# Main.net
KiCad netlist of a schematic drawn in EAGLE
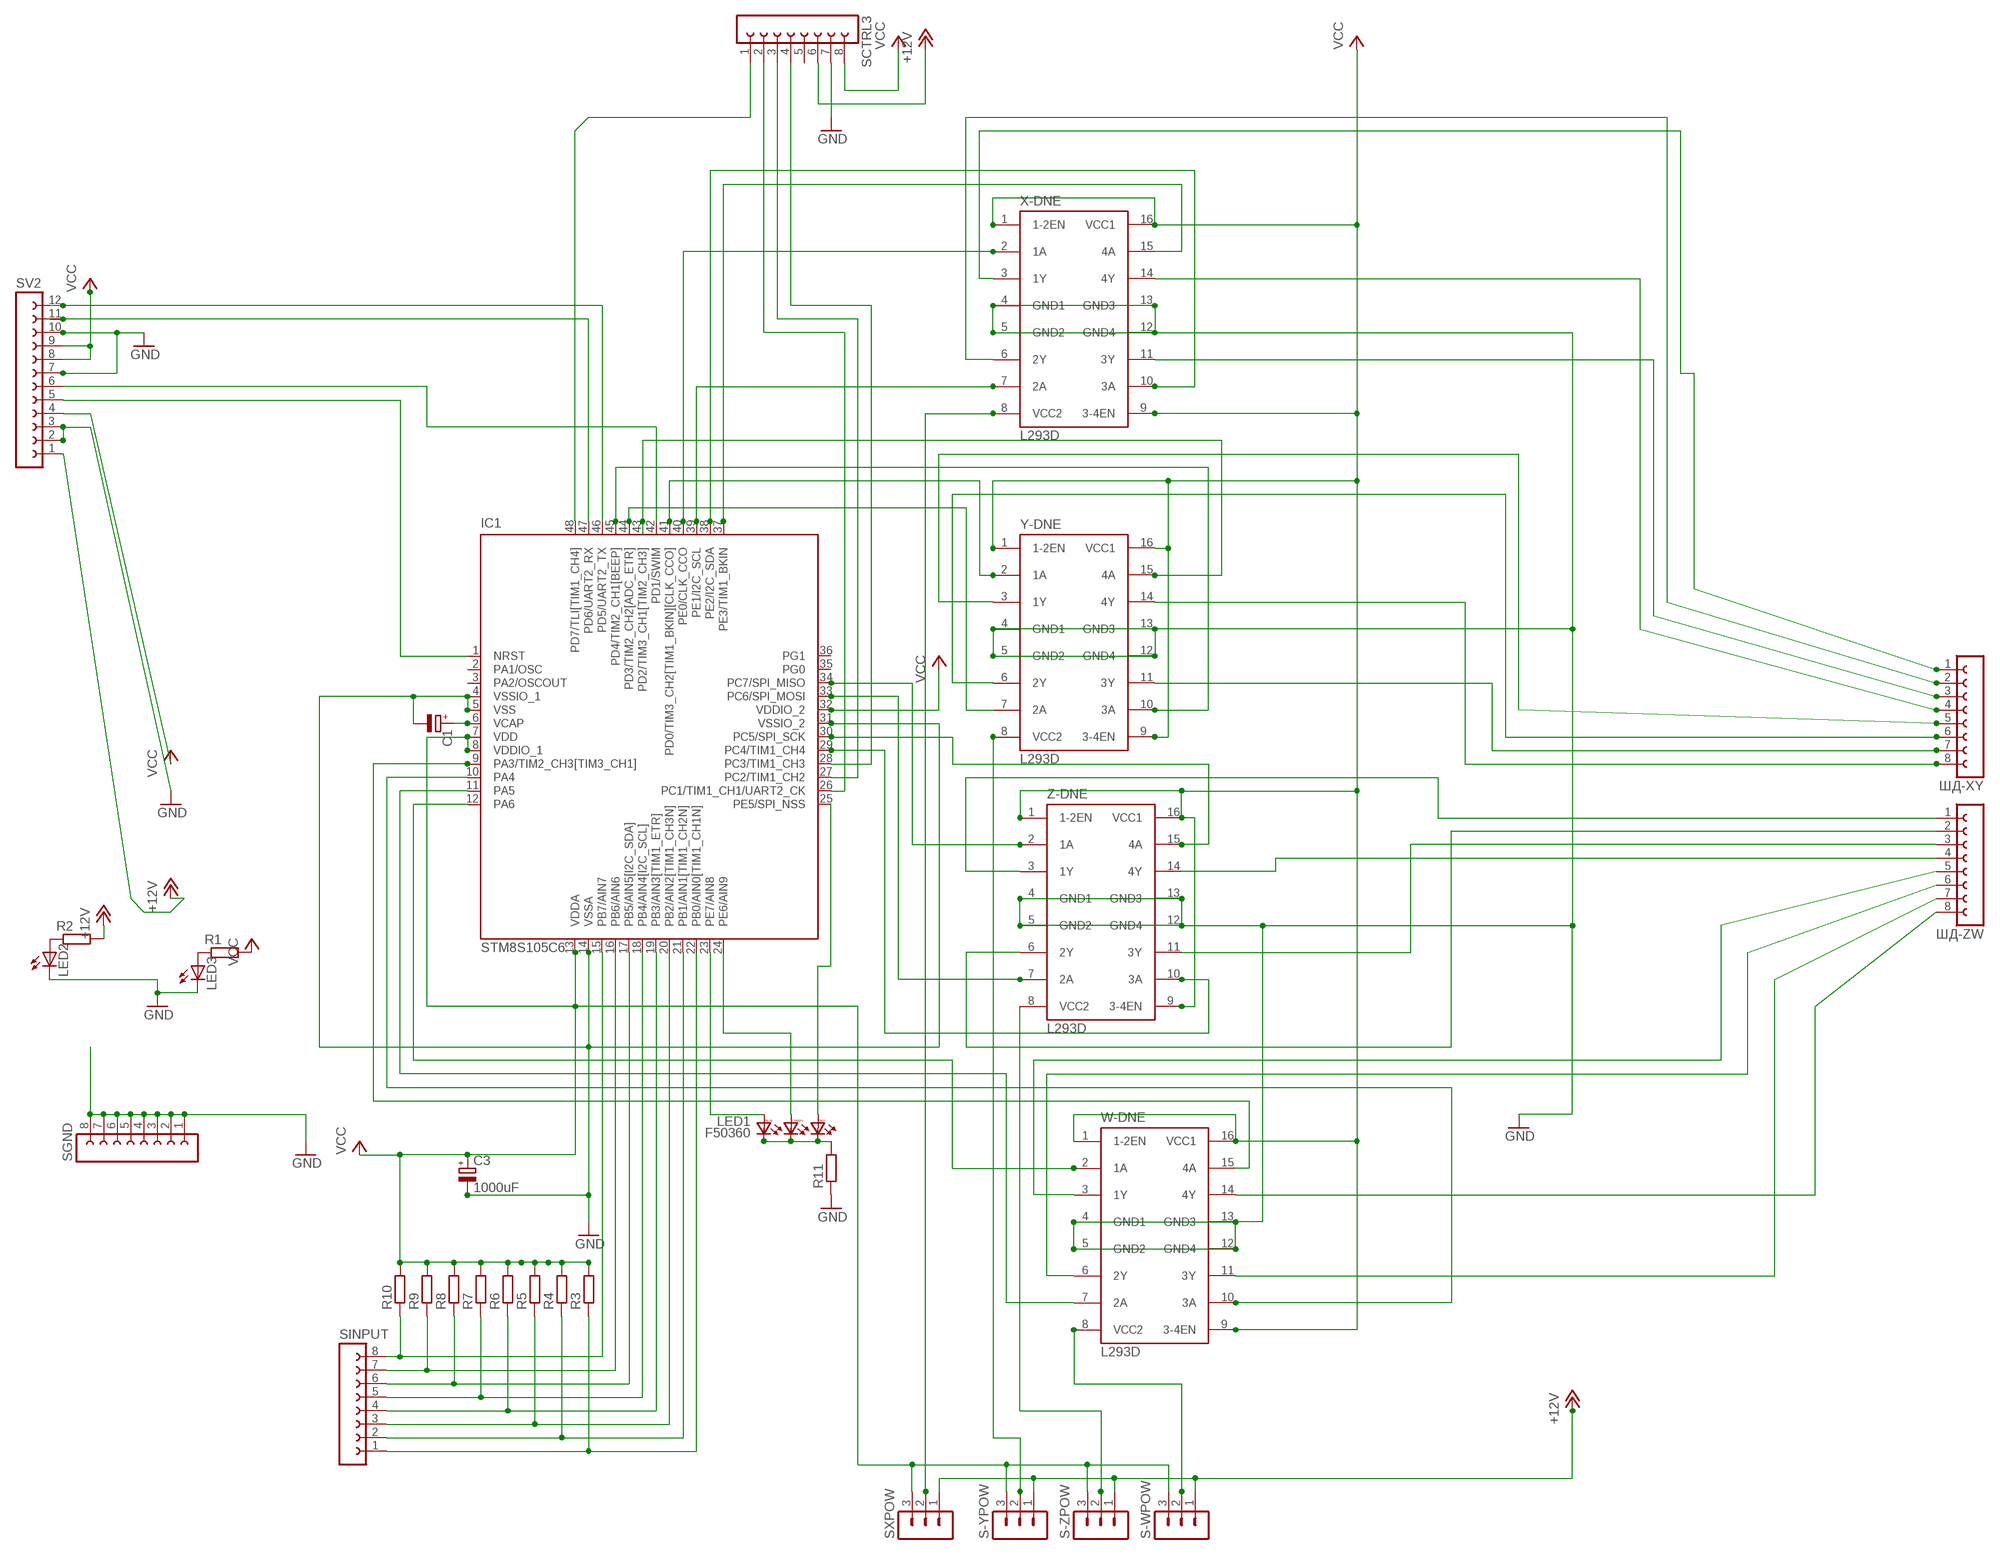
[diagram p0: schematic, sheet 1]

(export (version "E")
  (design (tool "Eeschema 10.0.6"))
  (components
    (comp (ref "C1")
      (value "CPOL-EU085CS-1AR")
      (footprint "eagle-import:085CS_1AR")
      (libsource (lib "eagle-import") (part "resistor_CPOL-EU085CS-1AR"))
    )
    (comp (ref "C3")
      (value "1000uF")
      (footprint "eagle-import:SANYO-OSCON_9E")
      (libsource (lib "eagle-import") (part "CPOL-EUSANYO_9E"))
    )
    (comp (ref "IC1")
      (value "STM8S105C6")
      (footprint "eagle-import:LQFP48-7X7")
      (fields (field (name "MPN") "STM8S105C6T6"))
      (libsource (lib "eagle-import") (part "STM8S105C6"))
    )
    (comp (ref "LED1")
      (value "F50360")
      (footprint "eagle-import:F50360")
      (libsource (lib "eagle-import") (part "F50360"))
    )
    (comp (ref "LED2")
      (value "LED3MM")
      (footprint "eagle-import:LED3MM")
      (libsource (lib "eagle-import") (part "LED3MM"))
    )
    (comp (ref "LED3")
      (value "LED3MM")
      (footprint "eagle-import:LED3MM")
      (libsource (lib "eagle-import") (part "LED3MM"))
    )
    (comp (ref "R1")
      (value "R-EU_0204/7")
      (footprint "eagle-import:0204_7")
      (libsource (lib "eagle-import") (part "R-EU_0204/7"))
    )
    (comp (ref "R2")
      (value "R-EU_0204/7")
      (footprint "eagle-import:0204_7")
      (libsource (lib "eagle-import") (part "R-EU_0204/7"))
    )
    (comp (ref "R3")
      (value "R-EU_M0805")
      (footprint "eagle-import:M0805")
      (libsource (lib "eagle-import") (part "R-EU_M0805"))
    )
    (comp (ref "R4")
      (value "R-EU_M0805")
      (footprint "eagle-import:M0805")
      (libsource (lib "eagle-import") (part "R-EU_M0805"))
    )
    (comp (ref "R5")
      (value "R-EU_M0805")
      (footprint "eagle-import:M0805")
      (libsource (lib "eagle-import") (part "R-EU_M0805"))
    )
    (comp (ref "R6")
      (value "R-EU_M0805")
      (footprint "eagle-import:M0805")
      (libsource (lib "eagle-import") (part "R-EU_M0805"))
    )
    (comp (ref "R7")
      (value "R-EU_M0805")
      (footprint "eagle-import:M0805")
      (libsource (lib "eagle-import") (part "R-EU_M0805"))
    )
    (comp (ref "R8")
      (value "R-EU_M0805")
      (footprint "eagle-import:M0805")
      (libsource (lib "eagle-import") (part "R-EU_M0805"))
    )
    (comp (ref "R9")
      (value "R-EU_M0805")
      (footprint "eagle-import:M0805")
      (libsource (lib "eagle-import") (part "R-EU_M0805"))
    )
    (comp (ref "R10")
      (value "R-EU_M0805")
      (footprint "eagle-import:M0805")
      (libsource (lib "eagle-import") (part "R-EU_M0805"))
    )
    (comp (ref "R11")
      (value "R-EU_0204/7")
      (footprint "eagle-import:0204_7")
      (libsource (lib "eagle-import") (part "R-EU_0204/7"))
    )
    (comp (ref "S-WPOW")
      (value "MA03-1")
      (footprint "eagle-import:MA03-1")
      (libsource (lib "eagle-import") (part "MA03-1"))
    )
    (comp (ref "S-YPOW")
      (value "MA03-1")
      (footprint "eagle-import:MA03-1")
      (libsource (lib "eagle-import") (part "MA03-1"))
    )
    (comp (ref "S-ZPOW")
      (value "MA03-1")
      (footprint "eagle-import:MA03-1")
      (libsource (lib "eagle-import") (part "MA03-1"))
    )
    (comp (ref "SCTRL3")
      (value "FE08-1")
      (footprint "eagle-import:FE08")
      (fields (field (name "OC_FARNELL") "unknown") (field (name "OC_NEWARK") "unknown"))
      (libsource (lib "eagle-import") (part "FE08-1"))
    )
    (comp (ref "SGND")
      (value "FE08-1")
      (footprint "eagle-import:FE08")
      (fields (field (name "OC_FARNELL") "unknown") (field (name "OC_NEWARK") "unknown"))
      (libsource (lib "eagle-import") (part "FE08-1"))
    )
    (comp (ref "SINPUT")
      (value "FE08-1")
      (footprint "eagle-import:FE08")
      (fields (field (name "OC_FARNELL") "unknown") (field (name "OC_NEWARK") "unknown"))
      (libsource (lib "eagle-import") (part "FE08-1"))
    )
    (comp (ref "SV2")
      (value "FE12-1")
      (footprint "eagle-import:FE12")
      (libsource (lib "eagle-import") (part "FE12-1"))
    )
    (comp (ref "SXPOW")
      (value "MA03-1")
      (footprint "eagle-import:MA03-1")
      (libsource (lib "eagle-import") (part "MA03-1"))
    )
    (comp (ref "W-DNE")
      (value "L293D")
      (footprint "eagle-import:DIL16")
      (libsource (lib "eagle-import") (part "L293D"))
    )
    (comp (ref "X-DNE")
      (value "L293D")
      (footprint "eagle-import:DIL16")
      (libsource (lib "eagle-import") (part "L293D"))
    )
    (comp (ref "Y-DNE")
      (value "L293D")
      (footprint "eagle-import:DIL16")
      (libsource (lib "eagle-import") (part "L293D"))
    )
    (comp (ref "Z-DNE")
      (value "L293D")
      (footprint "eagle-import:DIL16")
      (libsource (lib "eagle-import") (part "L293D"))
    )
    (comp (ref "ШД-XY")
      (value "FE08-1")
      (footprint "eagle-import:FE08")
      (libsource (lib "eagle-import") (part "FE08-1"))
    )
    (comp (ref "ШД-ZW")
      (value "FE08-1")
      (footprint "eagle-import:FE08")
      (libsource (lib "eagle-import") (part "FE08-1"))
    )
  )
  (nets
    (net (code "1") (name "+12V") (class "Default")
      (node (ref "R2") (pin "2") (pinfunction "2_2") (pintype "passive"))
      (node (ref "S-WPOW") (pin "1") (pinfunction "1_1") (pintype "passive"))
      (node (ref "S-YPOW") (pin "1") (pinfunction "1_1") (pintype "passive"))
      (node (ref "S-ZPOW") (pin "1") (pinfunction "1_1") (pintype "passive"))
      (node (ref "SCTRL3") (pin "6") (pinfunction "6_6") (pintype "passive"))
      (node (ref "SV2") (pin "1") (pinfunction "1_1") (pintype "passive"))
      (node (ref "SXPOW") (pin "1") (pinfunction "1_1") (pintype "passive"))
    )
    (net (code "2") (name "GND") (class "Default")
      (node (ref "C1") (pin "-") (pinfunction "-_-") (pintype "passive"))
      (node (ref "C3") (pin "-") (pinfunction "-_-") (pintype "passive"))
      (node (ref "IC1") (pin "14") (pinfunction "VSSA_14") (pintype "power_in"))
      (node (ref "IC1") (pin "31") (pinfunction "VSSIO_2_31") (pintype "power_in"))
      (node (ref "IC1") (pin "4") (pinfunction "VSSIO_1_4") (pintype "power_in"))
      (node (ref "IC1") (pin "5") (pinfunction "VSS_5") (pintype "power_in"))
      (node (ref "LED2") (pin "K") (pinfunction "C_K") (pintype "passive"))
      (node (ref "LED3") (pin "K") (pinfunction "C_K") (pintype "passive"))
      (node (ref "R11") (pin "1") (pinfunction "1_1") (pintype "passive"))
      (node (ref "SCTRL3") (pin "7") (pinfunction "7_7") (pintype "passive"))
      (node (ref "SGND") (pin "1") (pinfunction "1_1") (pintype "passive"))
      (node (ref "SGND") (pin "2") (pinfunction "2_2") (pintype "passive"))
      (node (ref "SGND") (pin "3") (pinfunction "3_3") (pintype "passive"))
      (node (ref "SGND") (pin "4") (pinfunction "4_4") (pintype "passive"))
      (node (ref "SGND") (pin "5") (pinfunction "5_5") (pintype "passive"))
      (node (ref "SGND") (pin "6") (pinfunction "6_6") (pintype "passive"))
      (node (ref "SGND") (pin "7") (pinfunction "7_7") (pintype "passive"))
      (node (ref "SGND") (pin "8") (pinfunction "8_8") (pintype "passive"))
      (node (ref "SV2") (pin "10") (pinfunction "10_10") (pintype "passive"))
      (node (ref "SV2") (pin "2") (pinfunction "2_2") (pintype "passive"))
      (node (ref "SV2") (pin "3") (pinfunction "3_3") (pintype "passive"))
      (node (ref "SV2") (pin "7") (pinfunction "7_7") (pintype "passive"))
      (node (ref "W-DNE") (pin "12") (pinfunction "GND4_12") (pintype "power_in"))
      (node (ref "W-DNE") (pin "13") (pinfunction "GND3_13") (pintype "power_in"))
      (node (ref "W-DNE") (pin "4") (pinfunction "GND1_4") (pintype "power_in"))
      (node (ref "W-DNE") (pin "5") (pinfunction "GND2_5") (pintype "power_in"))
      (node (ref "X-DNE") (pin "12") (pinfunction "GND4_12") (pintype "power_in"))
      (node (ref "X-DNE") (pin "13") (pinfunction "GND3_13") (pintype "power_in"))
      (node (ref "X-DNE") (pin "4") (pinfunction "GND1_4") (pintype "power_in"))
      (node (ref "X-DNE") (pin "5") (pinfunction "GND2_5") (pintype "power_in"))
      (node (ref "Y-DNE") (pin "12") (pinfunction "GND4_12") (pintype "power_in"))
      (node (ref "Y-DNE") (pin "13") (pinfunction "GND3_13") (pintype "power_in"))
      (node (ref "Y-DNE") (pin "4") (pinfunction "GND1_4") (pintype "power_in"))
      (node (ref "Y-DNE") (pin "5") (pinfunction "GND2_5") (pintype "power_in"))
      (node (ref "Z-DNE") (pin "12") (pinfunction "GND4_12") (pintype "power_in"))
      (node (ref "Z-DNE") (pin "13") (pinfunction "GND3_13") (pintype "power_in"))
      (node (ref "Z-DNE") (pin "4") (pinfunction "GND1_4") (pintype "power_in"))
      (node (ref "Z-DNE") (pin "5") (pinfunction "GND2_5") (pintype "power_in"))
    )
    (net (code "3") (name "Net-(IC1-NRST)") (class "Default")
      (node (ref "IC1") (pin "1") (pinfunction "NRST_1") (pintype "bidirectional"))
      (node (ref "SV2") (pin "5") (pinfunction "5_5") (pintype "passive"))
    )
    (net (code "4") (name "Net-(IC1-PA3{slash}TIM2_CH3[TIM3_CH1])") (class "Default")
      (node (ref "IC1") (pin "9") (pinfunction "PA3/TIM2_CH3[TIM3_CH1]_9") (pintype "bidirectional"))
      (node (ref "W-DNE") (pin "15") (pinfunction "4A_15") (pintype "input"))
    )
    (net (code "5") (name "Net-(IC1-PA4)") (class "Default")
      (node (ref "IC1") (pin "10") (pinfunction "PA4_10") (pintype "bidirectional"))
      (node (ref "W-DNE") (pin "10") (pinfunction "3A_10") (pintype "input"))
    )
    (net (code "6") (name "Net-(IC1-PA5)") (class "Default")
      (node (ref "IC1") (pin "11") (pinfunction "PA5_11") (pintype "bidirectional"))
      (node (ref "W-DNE") (pin "7") (pinfunction "2A_7") (pintype "input"))
    )
    (net (code "7") (name "Net-(IC1-PA6)") (class "Default")
      (node (ref "IC1") (pin "12") (pinfunction "PA6_12") (pintype "bidirectional"))
      (node (ref "W-DNE") (pin "2") (pinfunction "1A_2") (pintype "input"))
    )
    (net (code "8") (name "Net-(IC1-PB0{slash}AIN0[TIM1_CH1N])") (class "Default")
      (node (ref "IC1") (pin "22") (pinfunction "PB0/AIN0[TIM1_CH1N]_22") (pintype "bidirectional"))
      (node (ref "R3") (pin "1") (pinfunction "1_1") (pintype "passive"))
      (node (ref "SINPUT") (pin "1") (pinfunction "1_1") (pintype "passive"))
    )
    (net (code "9") (name "Net-(IC1-PB1{slash}AIN1[TIM1_CH2N])") (class "Default")
      (node (ref "IC1") (pin "21") (pinfunction "PB1/AIN1[TIM1_CH2N]_21") (pintype "bidirectional"))
      (node (ref "R4") (pin "1") (pinfunction "1_1") (pintype "passive"))
      (node (ref "SINPUT") (pin "2") (pinfunction "2_2") (pintype "passive"))
    )
    (net (code "10") (name "Net-(IC1-PB2{slash}AIN2[TIM1_CH3N])") (class "Default")
      (node (ref "IC1") (pin "20") (pinfunction "PB2/AIN2[TIM1_CH3N]_20") (pintype "bidirectional"))
      (node (ref "R5") (pin "1") (pinfunction "1_1") (pintype "passive"))
      (node (ref "SINPUT") (pin "3") (pinfunction "3_3") (pintype "passive"))
    )
    (net (code "11") (name "Net-(IC1-PB3{slash}AIN3[TIM1_ETR])") (class "Default")
      (node (ref "IC1") (pin "19") (pinfunction "PB3/AIN3[TIM1_ETR]_19") (pintype "bidirectional"))
      (node (ref "R6") (pin "1") (pinfunction "1_1") (pintype "passive"))
      (node (ref "SINPUT") (pin "4") (pinfunction "4_4") (pintype "passive"))
    )
    (net (code "12") (name "Net-(IC1-PB4{slash}AIN4[I2C_SCL])") (class "Default")
      (node (ref "IC1") (pin "18") (pinfunction "PB4/AIN4[I2C_SCL]_18") (pintype "bidirectional"))
      (node (ref "R7") (pin "1") (pinfunction "1_1") (pintype "passive"))
      (node (ref "SINPUT") (pin "5") (pinfunction "5_5") (pintype "passive"))
    )
    (net (code "13") (name "Net-(IC1-PB5{slash}AIN5[I2C_SDA])") (class "Default")
      (node (ref "IC1") (pin "17") (pinfunction "PB5/AIN5[I2C_SDA]_17") (pintype "bidirectional"))
      (node (ref "R8") (pin "1") (pinfunction "1_1") (pintype "passive"))
      (node (ref "SINPUT") (pin "6") (pinfunction "6_6") (pintype "passive"))
    )
    (net (code "14") (name "Net-(IC1-PB6{slash}AIN6)") (class "Default")
      (node (ref "IC1") (pin "16") (pinfunction "PB6/AIN6_16") (pintype "bidirectional"))
      (node (ref "R9") (pin "1") (pinfunction "1_1") (pintype "passive"))
      (node (ref "SINPUT") (pin "7") (pinfunction "7_7") (pintype "passive"))
    )
    (net (code "15") (name "Net-(IC1-PB7{slash}AIN7)") (class "Default")
      (node (ref "IC1") (pin "15") (pinfunction "PB7/AIN7_15") (pintype "bidirectional"))
      (node (ref "R10") (pin "1") (pinfunction "1_1") (pintype "passive"))
      (node (ref "SINPUT") (pin "8") (pinfunction "8_8") (pintype "passive"))
    )
    (net (code "16") (name "Net-(IC1-PC1{slash}TIM1_CH1{slash}UART2_CK)") (class "Default")
      (node (ref "IC1") (pin "26") (pinfunction "PC1/TIM1_CH1/UART2_CK_26") (pintype "bidirectional"))
      (node (ref "SCTRL3") (pin "2") (pinfunction "2_2") (pintype "passive"))
    )
    (net (code "17") (name "Net-(IC1-PC2{slash}TIM1_CH2)") (class "Default")
      (node (ref "IC1") (pin "27") (pinfunction "PC2/TIM1_CH2_27") (pintype "bidirectional"))
      (node (ref "SCTRL3") (pin "3") (pinfunction "3_3") (pintype "passive"))
    )
    (net (code "18") (name "Net-(IC1-PC3{slash}TIM1_CH3)") (class "Default")
      (node (ref "IC1") (pin "28") (pinfunction "PC3/TIM1_CH3_28") (pintype "bidirectional"))
      (node (ref "SCTRL3") (pin "4") (pinfunction "4_4") (pintype "passive"))
    )
    (net (code "19") (name "Net-(IC1-PC4{slash}TIM1_CH4)") (class "Default")
      (node (ref "IC1") (pin "29") (pinfunction "PC4/TIM1_CH4_29") (pintype "bidirectional"))
      (node (ref "Z-DNE") (pin "10") (pinfunction "3A_10") (pintype "input"))
    )
    (net (code "20") (name "Net-(IC1-PC5{slash}SPI_SCK)") (class "Default")
      (node (ref "IC1") (pin "30") (pinfunction "PC5/SPI_SCK_30") (pintype "bidirectional"))
      (node (ref "Z-DNE") (pin "15") (pinfunction "4A_15") (pintype "input"))
    )
    (net (code "21") (name "Net-(IC1-PC6{slash}SPI_MOSI)") (class "Default")
      (node (ref "IC1") (pin "33") (pinfunction "PC6/SPI_MOSI_33") (pintype "bidirectional"))
      (node (ref "Z-DNE") (pin "7") (pinfunction "2A_7") (pintype "input"))
    )
    (net (code "22") (name "Net-(IC1-PC7{slash}SPI_MISO)") (class "Default")
      (node (ref "IC1") (pin "34") (pinfunction "PC7/SPI_MISO_34") (pintype "bidirectional"))
      (node (ref "Z-DNE") (pin "2") (pinfunction "1A_2") (pintype "input"))
    )
    (net (code "23") (name "Net-(IC1-PD0{slash}TIM3_CH2[TIM1_BKIN][CLK_CCO])") (class "Default")
      (node (ref "IC1") (pin "41") (pinfunction "PD0/TIM3_CH2[TIM1_BKIN][CLK_CCO]_41") (pintype "bidirectional"))
      (node (ref "Y-DNE") (pin "2") (pinfunction "1A_2") (pintype "input"))
    )
    (net (code "24") (name "Net-(IC1-PD1{slash}SWIM)") (class "Default")
      (node (ref "IC1") (pin "42") (pinfunction "PD1/SWIM_42") (pintype "bidirectional"))
      (node (ref "SV2") (pin "6") (pinfunction "6_6") (pintype "passive"))
    )
    (net (code "25") (name "Net-(IC1-PD2{slash}TIM3_CH1[TIM2_CH3])") (class "Default")
      (node (ref "IC1") (pin "43") (pinfunction "PD2/TIM3_CH1[TIM2_CH3]_43") (pintype "bidirectional"))
      (node (ref "Y-DNE") (pin "15") (pinfunction "4A_15") (pintype "input"))
    )
    (net (code "26") (name "Net-(IC1-PD3{slash}TIM2_CH2[ADC_ETR])") (class "Default")
      (node (ref "IC1") (pin "44") (pinfunction "PD3/TIM2_CH2[ADC_ETR]_44") (pintype "bidirectional"))
      (node (ref "Y-DNE") (pin "7") (pinfunction "2A_7") (pintype "input"))
    )
    (net (code "27") (name "Net-(IC1-PD4{slash}TIM2_CH1[BEEP])") (class "Default")
      (node (ref "IC1") (pin "45") (pinfunction "PD4/TIM2_CH1[BEEP]_45") (pintype "bidirectional"))
      (node (ref "Y-DNE") (pin "10") (pinfunction "3A_10") (pintype "input"))
    )
    (net (code "28") (name "Net-(IC1-PD5{slash}UART2_TX)") (class "Default")
      (node (ref "IC1") (pin "46") (pinfunction "PD5/UART2_TX_46") (pintype "bidirectional"))
      (node (ref "SV2") (pin "12") (pinfunction "12_12") (pintype "passive"))
    )
    (net (code "29") (name "Net-(IC1-PD6{slash}UART2_RX)") (class "Default")
      (node (ref "IC1") (pin "47") (pinfunction "PD6/UART2_RX_47") (pintype "bidirectional"))
      (node (ref "SV2") (pin "11") (pinfunction "11_11") (pintype "passive"))
    )
    (net (code "30") (name "Net-(IC1-PD7{slash}TLI[TIM1_CH4])") (class "Default")
      (node (ref "IC1") (pin "48") (pinfunction "PD7/TLI[TIM1_CH4]_48") (pintype "bidirectional"))
      (node (ref "SCTRL3") (pin "1") (pinfunction "1_1") (pintype "passive"))
    )
    (net (code "31") (name "Net-(IC1-PE0{slash}CLK_CCO)") (class "Default")
      (node (ref "IC1") (pin "40") (pinfunction "PE0/CLK_CCO_40") (pintype "bidirectional"))
      (node (ref "X-DNE") (pin "2") (pinfunction "1A_2") (pintype "input"))
    )
    (net (code "32") (name "Net-(IC1-PE1{slash}I2C_SCL)") (class "Default")
      (node (ref "IC1") (pin "39") (pinfunction "PE1/I2C_SCL_39") (pintype "bidirectional"))
      (node (ref "X-DNE") (pin "7") (pinfunction "2A_7") (pintype "input"))
    )
    (net (code "33") (name "Net-(IC1-PE2{slash}I2C_SDA)") (class "Default")
      (node (ref "IC1") (pin "38") (pinfunction "PE2/I2C_SDA_38") (pintype "bidirectional"))
      (node (ref "X-DNE") (pin "10") (pinfunction "3A_10") (pintype "input"))
    )
    (net (code "34") (name "Net-(IC1-PE3{slash}TIM1_BKIN)") (class "Default")
      (node (ref "IC1") (pin "37") (pinfunction "PE3/TIM1_BKIN_37") (pintype "bidirectional"))
      (node (ref "X-DNE") (pin "15") (pinfunction "4A_15") (pintype "input"))
    )
    (net (code "35") (name "Net-(IC1-PE5{slash}SPI_NSS)") (class "Default")
      (node (ref "IC1") (pin "25") (pinfunction "PE5/SPI_NSS_25") (pintype "bidirectional"))
      (node (ref "LED1") (pin "RA") (pinfunction "RA_RA") (pintype "passive"))
    )
    (net (code "36") (name "Net-(IC1-PE6{slash}AIN9)") (class "Default")
      (node (ref "IC1") (pin "24") (pinfunction "PE6/AIN9_24") (pintype "bidirectional"))
      (node (ref "LED1") (pin "GA") (pinfunction "GA_GA") (pintype "passive"))
    )
    (net (code "37") (name "Net-(IC1-PE7{slash}AIN8)") (class "Default")
      (node (ref "IC1") (pin "23") (pinfunction "PE7/AIN8_23") (pintype "bidirectional"))
      (node (ref "LED1") (pin "BA") (pinfunction "BA_BA") (pintype "passive"))
    )
    (net (code "38") (name "Net-(IC1-VCAP)") (class "Default")
      (node (ref "C1") (pin "+") (pinfunction "+_+") (pintype "passive"))
      (node (ref "IC1") (pin "6") (pinfunction "VCAP_6") (pintype "power_in"))
    )
    (net (code "39") (name "Net-(LED1-PadBC)") (class "Default")
      (node (ref "LED1") (pin "BC") (pinfunction "BC_BC") (pintype "passive"))
      (node (ref "LED1") (pin "GC") (pinfunction "GC_GC") (pintype "passive"))
      (node (ref "LED1") (pin "RC") (pinfunction "RC_RC") (pintype "passive"))
      (node (ref "R11") (pin "2") (pinfunction "2_2") (pintype "passive"))
    )
    (net (code "40") (name "Net-(LED2-PadA)") (class "Default")
      (node (ref "LED2") (pin "A") (pinfunction "A_A") (pintype "passive"))
      (node (ref "R2") (pin "1") (pinfunction "1_1") (pintype "passive"))
    )
    (net (code "41") (name "Net-(LED3-PadA)") (class "Default")
      (node (ref "LED3") (pin "A") (pinfunction "A_A") (pintype "passive"))
      (node (ref "R1") (pin "1") (pinfunction "1_1") (pintype "passive"))
    )
    (net (code "42") (name "Net-(W-DNE-1Y)") (class "Default")
      (node (ref "W-DNE") (pin "3") (pinfunction "1Y_3") (pintype "output"))
      (node (ref "ШД-ZW") (pin "5") (pinfunction "5_5") (pintype "passive"))
    )
    (net (code "43") (name "Net-(W-DNE-2Y)") (class "Default")
      (node (ref "W-DNE") (pin "6") (pinfunction "2Y_6") (pintype "output"))
      (node (ref "ШД-ZW") (pin "6") (pinfunction "6_6") (pintype "passive"))
    )
    (net (code "44") (name "Net-(W-DNE-3Y)") (class "Default")
      (node (ref "W-DNE") (pin "11") (pinfunction "3Y_11") (pintype "output"))
      (node (ref "ШД-ZW") (pin "7") (pinfunction "7_7") (pintype "passive"))
    )
    (net (code "45") (name "Net-(W-DNE-4Y)") (class "Default")
      (node (ref "W-DNE") (pin "14") (pinfunction "4Y_14") (pintype "output"))
      (node (ref "ШД-ZW") (pin "8") (pinfunction "8_8") (pintype "passive"))
    )
    (net (code "46") (name "Net-(W-DNE-VCC2)") (class "Default")
      (node (ref "S-WPOW") (pin "2") (pinfunction "2_2") (pintype "passive"))
      (node (ref "W-DNE") (pin "8") (pinfunction "VCC2_8") (pintype "power_in"))
    )
    (net (code "47") (name "Net-(X-DNE-1Y)") (class "Default")
      (node (ref "X-DNE") (pin "3") (pinfunction "1Y_3") (pintype "output"))
      (node (ref "ШД-XY") (pin "1") (pinfunction "1_1") (pintype "passive"))
    )
    (net (code "48") (name "Net-(X-DNE-2Y)") (class "Default")
      (node (ref "X-DNE") (pin "6") (pinfunction "2Y_6") (pintype "output"))
      (node (ref "ШД-XY") (pin "2") (pinfunction "2_2") (pintype "passive"))
    )
    (net (code "49") (name "Net-(X-DNE-3Y)") (class "Default")
      (node (ref "X-DNE") (pin "11") (pinfunction "3Y_11") (pintype "output"))
      (node (ref "ШД-XY") (pin "3") (pinfunction "3_3") (pintype "passive"))
    )
    (net (code "50") (name "Net-(X-DNE-4Y)") (class "Default")
      (node (ref "X-DNE") (pin "14") (pinfunction "4Y_14") (pintype "output"))
      (node (ref "ШД-XY") (pin "4") (pinfunction "4_4") (pintype "passive"))
    )
    (net (code "51") (name "Net-(X-DNE-VCC2)") (class "Default")
      (node (ref "SXPOW") (pin "2") (pinfunction "2_2") (pintype "passive"))
      (node (ref "X-DNE") (pin "8") (pinfunction "VCC2_8") (pintype "power_in"))
    )
    (net (code "52") (name "Net-(Y-DNE-1Y)") (class "Default")
      (node (ref "Y-DNE") (pin "3") (pinfunction "1Y_3") (pintype "output"))
      (node (ref "ШД-XY") (pin "5") (pinfunction "5_5") (pintype "passive"))
    )
    (net (code "53") (name "Net-(Y-DNE-2Y)") (class "Default")
      (node (ref "Y-DNE") (pin "6") (pinfunction "2Y_6") (pintype "output"))
      (node (ref "ШД-XY") (pin "6") (pinfunction "6_6") (pintype "passive"))
    )
    (net (code "54") (name "Net-(Y-DNE-3Y)") (class "Default")
      (node (ref "Y-DNE") (pin "11") (pinfunction "3Y_11") (pintype "output"))
      (node (ref "ШД-XY") (pin "7") (pinfunction "7_7") (pintype "passive"))
    )
    (net (code "55") (name "Net-(Y-DNE-4Y)") (class "Default")
      (node (ref "Y-DNE") (pin "14") (pinfunction "4Y_14") (pintype "output"))
      (node (ref "ШД-XY") (pin "8") (pinfunction "8_8") (pintype "passive"))
    )
    (net (code "56") (name "Net-(Y-DNE-VCC2)") (class "Default")
      (node (ref "S-YPOW") (pin "2") (pinfunction "2_2") (pintype "passive"))
      (node (ref "Y-DNE") (pin "8") (pinfunction "VCC2_8") (pintype "power_in"))
    )
    (net (code "57") (name "Net-(Z-DNE-1Y)") (class "Default")
      (node (ref "Z-DNE") (pin "3") (pinfunction "1Y_3") (pintype "output"))
      (node (ref "ШД-ZW") (pin "1") (pinfunction "1_1") (pintype "passive"))
    )
    (net (code "58") (name "Net-(Z-DNE-2Y)") (class "Default")
      (node (ref "Z-DNE") (pin "6") (pinfunction "2Y_6") (pintype "output"))
      (node (ref "ШД-ZW") (pin "2") (pinfunction "2_2") (pintype "passive"))
    )
    (net (code "59") (name "Net-(Z-DNE-3Y)") (class "Default")
      (node (ref "Z-DNE") (pin "11") (pinfunction "3Y_11") (pintype "output"))
      (node (ref "ШД-ZW") (pin "3") (pinfunction "3_3") (pintype "passive"))
    )
    (net (code "60") (name "Net-(Z-DNE-4Y)") (class "Default")
      (node (ref "Z-DNE") (pin "14") (pinfunction "4Y_14") (pintype "output"))
      (node (ref "ШД-ZW") (pin "4") (pinfunction "4_4") (pintype "passive"))
    )
    (net (code "61") (name "Net-(Z-DNE-VCC2)") (class "Default")
      (node (ref "S-ZPOW") (pin "2") (pinfunction "2_2") (pintype "passive"))
      (node (ref "Z-DNE") (pin "8") (pinfunction "VCC2_8") (pintype "power_in"))
    )
    (net (code "62") (name "VCC") (class "Default")
      (node (ref "C3") (pin "+") (pinfunction "+_+") (pintype "passive"))
      (node (ref "IC1") (pin "13") (pinfunction "VDDA_13") (pintype "power_in"))
      (node (ref "IC1") (pin "32") (pinfunction "VDDIO_2_32") (pintype "power_in"))
      (node (ref "IC1") (pin "7") (pinfunction "VDD_7") (pintype "power_in"))
      (node (ref "IC1") (pin "8") (pinfunction "VDDIO_1_8") (pintype "power_in"))
      (node (ref "R1") (pin "2") (pinfunction "2_2") (pintype "passive"))
      (node (ref "R10") (pin "2") (pinfunction "2_2") (pintype "passive"))
      (node (ref "R3") (pin "2") (pinfunction "2_2") (pintype "passive"))
      (node (ref "R4") (pin "2") (pinfunction "2_2") (pintype "passive"))
      (node (ref "R5") (pin "2") (pinfunction "2_2") (pintype "passive"))
      (node (ref "R6") (pin "2") (pinfunction "2_2") (pintype "passive"))
      (node (ref "R7") (pin "2") (pinfunction "2_2") (pintype "passive"))
      (node (ref "R8") (pin "2") (pinfunction "2_2") (pintype "passive"))
      (node (ref "R9") (pin "2") (pinfunction "2_2") (pintype "passive"))
      (node (ref "S-WPOW") (pin "3") (pinfunction "3_3") (pintype "passive"))
      (node (ref "S-YPOW") (pin "3") (pinfunction "3_3") (pintype "passive"))
      (node (ref "S-ZPOW") (pin "3") (pinfunction "3_3") (pintype "passive"))
      (node (ref "SCTRL3") (pin "8") (pinfunction "8_8") (pintype "passive"))
      (node (ref "SV2") (pin "4") (pinfunction "4_4") (pintype "passive"))
      (node (ref "SV2") (pin "8") (pinfunction "8_8") (pintype "passive"))
      (node (ref "SV2") (pin "9") (pinfunction "9_9") (pintype "passive"))
      (node (ref "SXPOW") (pin "3") (pinfunction "3_3") (pintype "passive"))
      (node (ref "W-DNE") (pin "1") (pinfunction "1-2EN_1") (pintype "input"))
      (node (ref "W-DNE") (pin "16") (pinfunction "VCC1_16") (pintype "power_in"))
      (node (ref "W-DNE") (pin "9") (pinfunction "3-4EN_9") (pintype "input"))
      (node (ref "X-DNE") (pin "1") (pinfunction "1-2EN_1") (pintype "input"))
      (node (ref "X-DNE") (pin "16") (pinfunction "VCC1_16") (pintype "power_in"))
      (node (ref "X-DNE") (pin "9") (pinfunction "3-4EN_9") (pintype "input"))
      (node (ref "Y-DNE") (pin "1") (pinfunction "1-2EN_1") (pintype "input"))
      (node (ref "Y-DNE") (pin "16") (pinfunction "VCC1_16") (pintype "power_in"))
      (node (ref "Y-DNE") (pin "9") (pinfunction "3-4EN_9") (pintype "input"))
      (node (ref "Z-DNE") (pin "1") (pinfunction "1-2EN_1") (pintype "input"))
      (node (ref "Z-DNE") (pin "16") (pinfunction "VCC1_16") (pintype "power_in"))
      (node (ref "Z-DNE") (pin "9") (pinfunction "3-4EN_9") (pintype "input"))
    )
    (net (code "63") (name "unconnected-(IC1-PA1{slash}OSC-Pad2)") (class "Default")
      (node (ref "IC1") (pin "2") (pinfunction "PA1/OSC_2") (pintype "bidirectional"))
    )
    (net (code "64") (name "unconnected-(IC1-PA2{slash}OSCOUT-Pad3)") (class "Default")
      (node (ref "IC1") (pin "3") (pinfunction "PA2/OSCOUT_3") (pintype "bidirectional"))
    )
    (net (code "65") (name "unconnected-(IC1-PG0-Pad35)") (class "Default")
      (node (ref "IC1") (pin "35") (pinfunction "PG0_35") (pintype "bidirectional"))
    )
    (net (code "66") (name "unconnected-(IC1-PG1-Pad36)") (class "Default")
      (node (ref "IC1") (pin "36") (pinfunction "PG1_36") (pintype "bidirectional"))
    )
    (net (code "67") (name "unconnected-(SCTRL3-Pad5)") (class "Default")
      (node (ref "SCTRL3") (pin "5") (pinfunction "5_5") (pintype "passive"))
    )
  )
)
